# wireless-therm-mk1.net
KiCad netlist of a schematic drawn in EAGLE
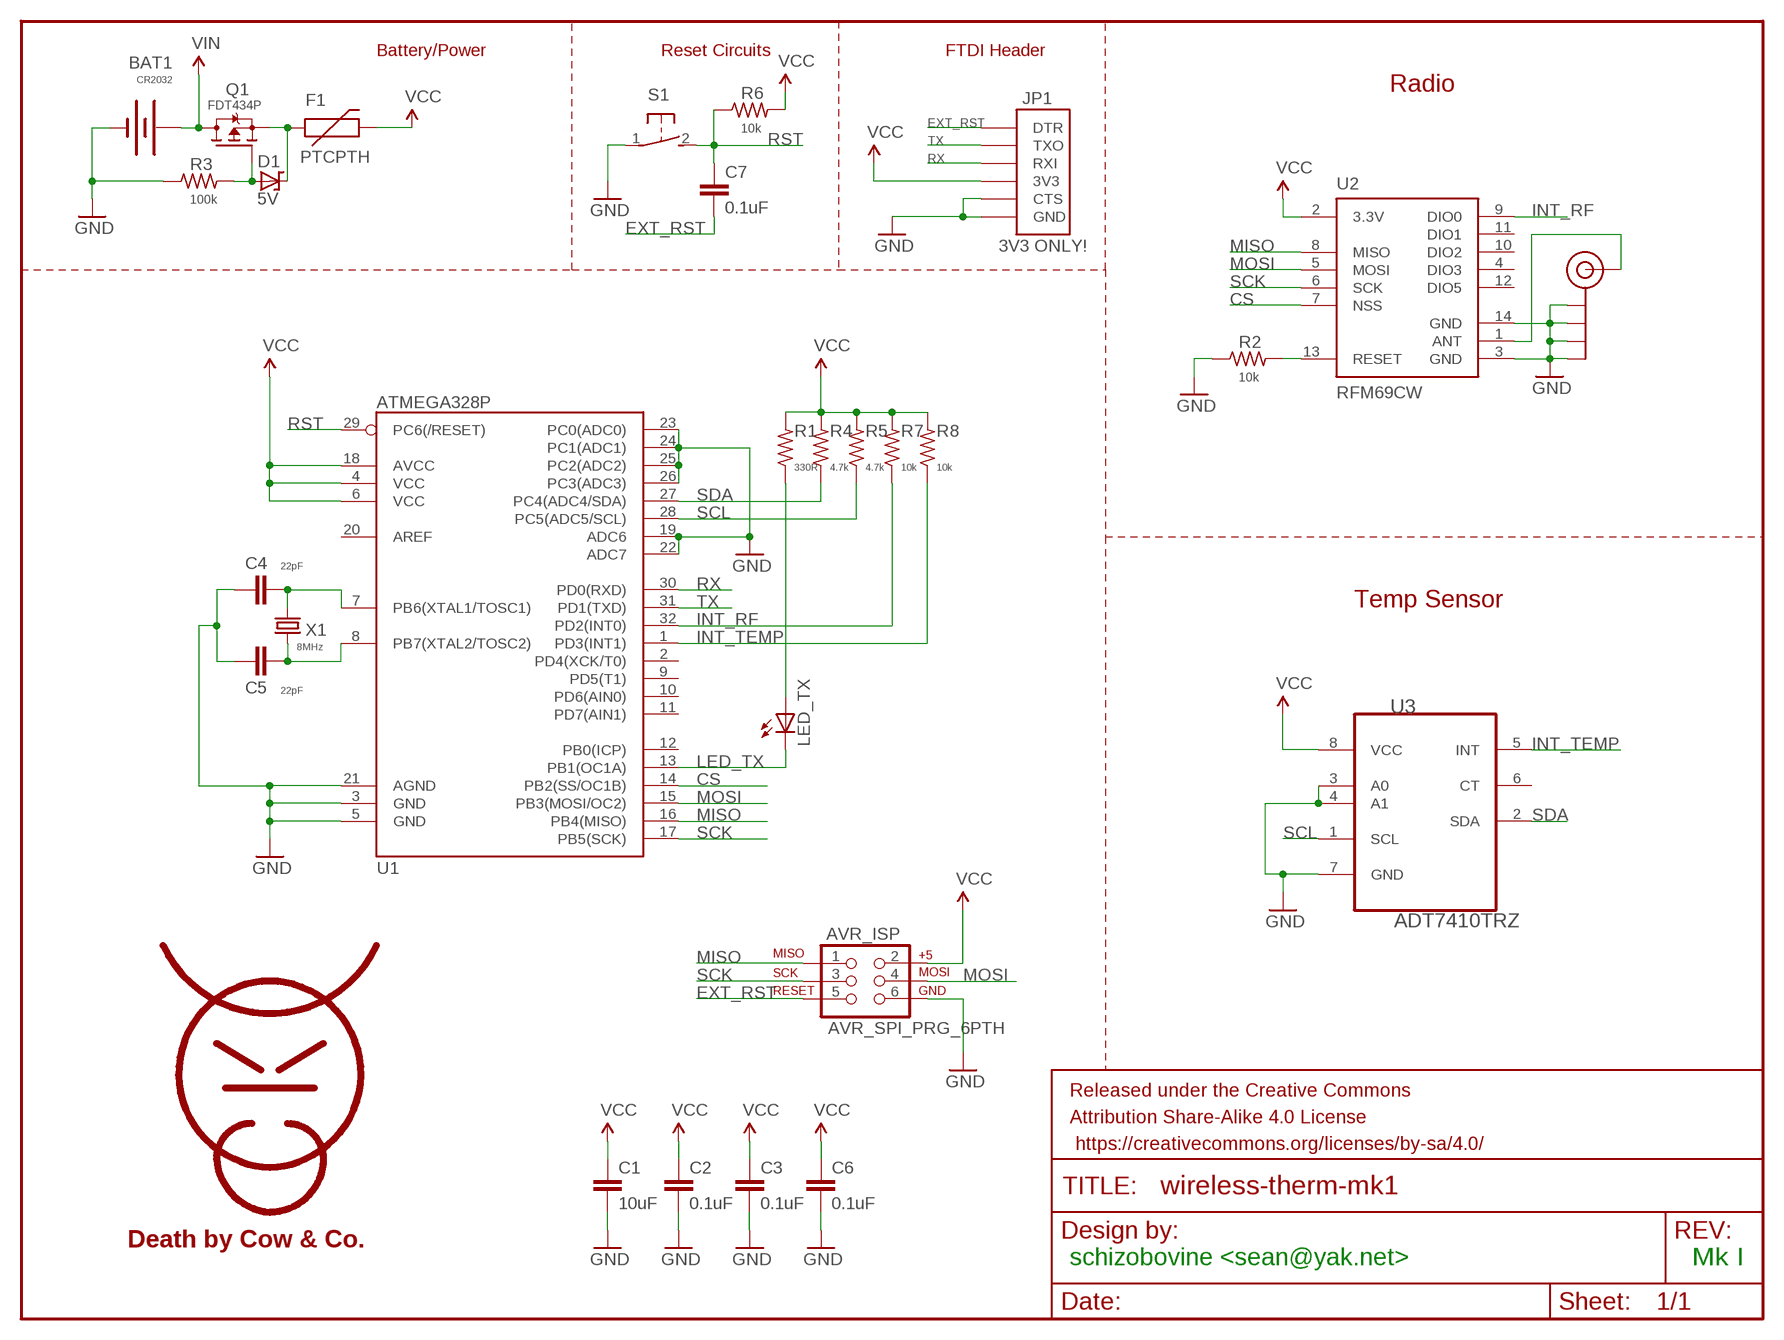
[diagram p0: schematic, sheet 1]

(export (version "E")
  (design (tool "Eeschema 10.0.6"))
  (components
    (comp (ref "AVR_ISP")
      (value "AVR_SPI_PRG_6PTH")
      (footprint "eagle-import:2X3")
      (libsource (lib "eagle-import") (part "AVR_SPI_PRG_6PTH"))
    )
    (comp (ref "BAT1")
      (value "CR2032")
      (footprint "eagle-import:BATTCON_20MM")
      (libsource (lib "eagle-import") (part "BATTERY20SMD"))
    )
    (comp (ref "C1")
      (value "10uF")
      (footprint "eagle-import:C050-025X075")
      (libsource (lib "eagle-import") (part "CAPACITOR-CERAMIC050-025X075"))
    )
    (comp (ref "C2")
      (value "0.1uF")
      (footprint "eagle-import:C025-024X044")
      (libsource (lib "eagle-import") (part "CAPACITOR-CERAMIC025-024X044"))
    )
    (comp (ref "C3")
      (value "0.1uF")
      (footprint "eagle-import:C025-024X044")
      (libsource (lib "eagle-import") (part "CAPACITOR-CERAMIC025-024X044"))
    )
    (comp (ref "C4")
      (value "22pF")
      (footprint "eagle-import:C025-025X050")
      (libsource (lib "eagle-import") (part "C-EU025-025X050"))
    )
    (comp (ref "C5")
      (value "22pF")
      (footprint "eagle-import:C025-025X050")
      (libsource (lib "eagle-import") (part "C-EU025-025X050"))
    )
    (comp (ref "C6")
      (value "0.1uF")
      (footprint "eagle-import:C025-024X044")
      (libsource (lib "eagle-import") (part "CAPACITOR-CERAMIC025-024X044"))
    )
    (comp (ref "C7")
      (value "0.1uF")
      (footprint "eagle-import:C025-024X044")
      (libsource (lib "eagle-import") (part "CAPACITOR-CERAMIC025-024X044"))
    )
    (comp (ref "D1")
      (value "5V")
      (footprint "eagle-import:DO34Z7")
      (libsource (lib "eagle-import") (part "DO-34ZDO-34Z"))
    )
    (comp (ref "F1")
      (value "PTCPTH")
      (footprint "eagle-import:PTC")
      (libsource (lib "eagle-import") (part "PTCPTH"))
    )
    (comp (ref "FRAME1")
      (value "FRAME-LETTER")
      (footprint "eagle-import:CREATIVE_COMMONS")
      (libsource (lib "eagle-import") (part "FRAME-LETTER"))
    )
    (comp (ref "JP1")
      (value "3V3 ONLY!")
      (footprint "eagle-import:FTDI_3V3")
      (libsource (lib "eagle-import") (part "FTDI_3V3"))
    )
    (comp (ref "LED_TX")
      (value "GREEN")
      (footprint "eagle-import:LED3MM")
      (libsource (lib "eagle-import") (part "LED3MM"))
    )
    (comp (ref "Q1")
      (value "FDT434P")
      (footprint "eagle-import:SOT223")
      (libsource (lib "eagle-import") (part "FDT434P"))
    )
    (comp (ref "R1")
      (value "330R")
      (footprint "eagle-import:0204_5")
      (libsource (lib "eagle-import") (part "R-US_0204/5"))
    )
    (comp (ref "R2")
      (value "10k")
      (footprint "eagle-import:0204_5")
      (libsource (lib "eagle-import") (part "R-US_0204/5"))
    )
    (comp (ref "R3")
      (value "100k")
      (footprint "eagle-import:0204_5")
      (libsource (lib "eagle-import") (part "R-US_0204/5"))
    )
    (comp (ref "R4")
      (value "4.7k")
      (footprint "eagle-import:0204_5")
      (libsource (lib "eagle-import") (part "R-US_0204/5"))
    )
    (comp (ref "R5")
      (value "4.7k")
      (footprint "eagle-import:0204_5")
      (libsource (lib "eagle-import") (part "R-US_0204/5"))
    )
    (comp (ref "R6")
      (value "10k")
      (footprint "eagle-import:0204_5")
      (libsource (lib "eagle-import") (part "R-US_0204/5"))
    )
    (comp (ref "R7")
      (value "10k")
      (footprint "eagle-import:0204_5")
      (libsource (lib "eagle-import") (part "R-US_0204/5"))
    )
    (comp (ref "R8")
      (value "10k")
      (footprint "eagle-import:0204_5")
      (libsource (lib "eagle-import") (part "R-US_0204/5"))
    )
    (comp (ref "S1")
      (value "DTS-3")
      (footprint "eagle-import:DTS-3")
      (libsource (lib "eagle-import") (part "DTS-3"))
    )
    (comp (ref "SMA_CON")
      (value "SMA_EDGE")
      (footprint "eagle-import:SMA-EDGE")
      (libsource (lib "eagle-import") (part "SMA_EDGE"))
    )
    (comp (ref "U$4")
      (value "COW")
      (footprint "eagle-import:COW")
      (libsource (lib "eagle-import") (part "COW"))
    )
    (comp (ref "U1")
      (value "ATMEGA328P")
      (footprint "eagle-import:TQFP32-08")
      (libsource (lib "eagle-import") (part "ATMEGA328_SMT"))
    )
    (comp (ref "U2")
      (value "RFM69CW")
      (footprint "eagle-import:RFM69CW-XXXS2")
      (libsource (lib "eagle-import") (part "RFM69CW"))
    )
    (comp (ref "U3")
      (value "ADT7410TRZ")
      (footprint "eagle-import:SOIC127P600X175-8N")
      (libsource (lib "eagle-import") (part "ADT7410TRZ"))
    )
    (comp (ref "X1")
      (value "8MHz")
      (footprint "eagle-import:HC49U70")
      (libsource (lib "eagle-import") (part "CRYSTALHC49U70"))
    )
  )
  (nets
    (net (code "1") (name "/CS") (class "Default")
      (node (ref "U1") (pin "14") (pinfunction "PB2(SS/OC1B)_14") (pintype "bidirectional"))
      (node (ref "U2") (pin "7") (pinfunction "NSS_7") (pintype "input"))
    )
    (net (code "2") (name "/EXT_RST") (class "Default")
      (node (ref "AVR_ISP") (pin "5") (pinfunction "5_5") (pintype "passive"))
      (node (ref "C7") (pin "2") (pinfunction "2_2") (pintype "passive"))
      (node (ref "JP1") (pin "P$1") (pinfunction "DTR_P$1") (pintype "bidirectional"))
    )
    (net (code "3") (name "/INT_RF") (class "Default")
      (node (ref "R7") (pin "1") (pinfunction "1_1") (pintype "passive"))
      (node (ref "U1") (pin "32") (pinfunction "PD2(INT0)_32") (pintype "bidirectional"))
      (node (ref "U2") (pin "9") (pinfunction "DIO0_9") (pintype "bidirectional"))
    )
    (net (code "4") (name "/INT_TEMP") (class "Default")
      (node (ref "R8") (pin "1") (pinfunction "1_1") (pintype "passive"))
      (node (ref "U1") (pin "1") (pinfunction "PD3(INT1)_1") (pintype "bidirectional"))
      (node (ref "U3") (pin "5") (pinfunction "INT_5") (pintype "output"))
    )
    (net (code "5") (name "/LED_TX") (class "Default")
      (node (ref "LED_TX") (pin "K") (pinfunction "C_K") (pintype "passive"))
      (node (ref "U1") (pin "13") (pinfunction "PB1(OC1A)_13") (pintype "bidirectional"))
    )
    (net (code "6") (name "/MISO") (class "Default")
      (node (ref "AVR_ISP") (pin "1") (pinfunction "1_1") (pintype "passive"))
      (node (ref "U1") (pin "16") (pinfunction "PB4(MISO)_16") (pintype "bidirectional"))
      (node (ref "U2") (pin "8") (pinfunction "MISO_8") (pintype "bidirectional"))
    )
    (net (code "7") (name "/MOSI") (class "Default")
      (node (ref "AVR_ISP") (pin "4") (pinfunction "4_4") (pintype "passive"))
      (node (ref "U1") (pin "15") (pinfunction "PB3(MOSI/OC2)_15") (pintype "bidirectional"))
      (node (ref "U2") (pin "5") (pinfunction "MOSI_5") (pintype "input"))
    )
    (net (code "8") (name "/RST") (class "Default")
      (node (ref "C7") (pin "1") (pinfunction "1_1") (pintype "passive"))
      (node (ref "R6") (pin "1") (pinfunction "1_1") (pintype "passive"))
      (node (ref "S1") (pin "2") (pinfunction "2_2") (pintype "passive"))
      (node (ref "U1") (pin "29") (pinfunction "PC6(/RESET)_29") (pintype "bidirectional"))
    )
    (net (code "9") (name "/RX") (class "Default")
      (node (ref "JP1") (pin "P$3") (pinfunction "RXI_P$3") (pintype "bidirectional"))
      (node (ref "U1") (pin "30") (pinfunction "PD0(RXD)_30") (pintype "bidirectional"))
    )
    (net (code "10") (name "/SCK") (class "Default")
      (node (ref "AVR_ISP") (pin "3") (pinfunction "3_3") (pintype "passive"))
      (node (ref "U1") (pin "17") (pinfunction "PB5(SCK)_17") (pintype "bidirectional"))
      (node (ref "U2") (pin "6") (pinfunction "SCK_6") (pintype "input"))
    )
    (net (code "11") (name "/SCL") (class "Default")
      (node (ref "R5") (pin "1") (pinfunction "1_1") (pintype "passive"))
      (node (ref "U1") (pin "28") (pinfunction "PC5(ADC5/SCL)_28") (pintype "bidirectional"))
      (node (ref "U3") (pin "1") (pinfunction "SCL_1") (pintype "input"))
    )
    (net (code "12") (name "/SDA") (class "Default")
      (node (ref "R4") (pin "1") (pinfunction "1_1") (pintype "passive"))
      (node (ref "U1") (pin "27") (pinfunction "PC4(ADC4/SDA)_27") (pintype "bidirectional"))
      (node (ref "U3") (pin "2") (pinfunction "SDA_2") (pintype "bidirectional"))
    )
    (net (code "13") (name "/TX") (class "Default")
      (node (ref "JP1") (pin "P$2") (pinfunction "TXO_P$2") (pintype "bidirectional"))
      (node (ref "U1") (pin "31") (pinfunction "PD1(TXD)_31") (pintype "bidirectional"))
    )
    (net (code "14") (name "GND") (class "Default")
      (node (ref "AVR_ISP") (pin "6") (pinfunction "6_6") (pintype "passive"))
      (node (ref "BAT1") (pin "2") (pinfunction "-_2") (pintype "power_in"))
      (node (ref "C1") (pin "2") (pinfunction "2_2") (pintype "passive"))
      (node (ref "C2") (pin "2") (pinfunction "2_2") (pintype "passive"))
      (node (ref "C3") (pin "2") (pinfunction "2_2") (pintype "passive"))
      (node (ref "C4") (pin "1") (pinfunction "1_1") (pintype "passive"))
      (node (ref "C5") (pin "1") (pinfunction "1_1") (pintype "passive"))
      (node (ref "C6") (pin "2") (pinfunction "2_2") (pintype "passive"))
      (node (ref "JP1") (pin "P$5") (pinfunction "CTS_P$5") (pintype "bidirectional"))
      (node (ref "JP1") (pin "P$6") (pinfunction "GND_P$6") (pintype "bidirectional"))
      (node (ref "R2") (pin "1") (pinfunction "1_1") (pintype "passive"))
      (node (ref "R3") (pin "1") (pinfunction "1_1") (pintype "passive"))
      (node (ref "S1") (pin "1") (pinfunction "1_1") (pintype "passive"))
      (node (ref "SMA_CON") (pin "GND@0") (pinfunction "GND_GND@0") (pintype "bidirectional"))
      (node (ref "SMA_CON") (pin "GND@1") (pinfunction "GND_GND@1") (pintype "bidirectional"))
      (node (ref "SMA_CON") (pin "GND@2") (pinfunction "GND_GND@2") (pintype "bidirectional"))
      (node (ref "SMA_CON") (pin "GND@3") (pinfunction "GND_GND@3") (pintype "bidirectional"))
      (node (ref "U1") (pin "19") (pinfunction "ADC6_19") (pintype "bidirectional"))
      (node (ref "U1") (pin "21") (pinfunction "AGND_21") (pintype "bidirectional"))
      (node (ref "U1") (pin "22") (pinfunction "ADC7_22") (pintype "bidirectional"))
      (node (ref "U1") (pin "23") (pinfunction "PC0(ADC0)_23") (pintype "bidirectional"))
      (node (ref "U1") (pin "24") (pinfunction "PC1(ADC1)_24") (pintype "bidirectional"))
      (node (ref "U1") (pin "25") (pinfunction "PC2(ADC2)_25") (pintype "bidirectional"))
      (node (ref "U1") (pin "26") (pinfunction "PC3(ADC3)_26") (pintype "bidirectional"))
      (node (ref "U1") (pin "3") (pinfunction "GND_3") (pintype "bidirectional"))
      (node (ref "U1") (pin "5") (pinfunction "GND_5") (pintype "bidirectional"))
      (node (ref "U2") (pin "14") (pinfunction "GND_14") (pintype "power_in"))
      (node (ref "U2") (pin "3") (pinfunction "GND_3") (pintype "power_in"))
      (node (ref "U3") (pin "3") (pinfunction "A0_3") (pintype "input"))
      (node (ref "U3") (pin "4") (pinfunction "A1_4") (pintype "input"))
      (node (ref "U3") (pin "7") (pinfunction "GND_7") (pintype "passive"))
    )
    (net (code "15") (name "Net-(F1-1)") (class "Default")
      (node (ref "D1") (pin "C") (pinfunction "C_C") (pintype "passive"))
      (node (ref "F1") (pin "P$1") (pinfunction "1_P$1") (pintype "bidirectional"))
      (node (ref "Q1") (pin "3") (pinfunction "S_3") (pintype "passive"))
    )
    (net (code "16") (name "Net-(LED_TX-PadA)") (class "Default")
      (node (ref "LED_TX") (pin "A") (pinfunction "A_A") (pintype "passive"))
      (node (ref "R1") (pin "1") (pinfunction "1_1") (pintype "passive"))
    )
    (net (code "17") (name "Net-(Q1-G)") (class "Default")
      (node (ref "D1") (pin "A") (pinfunction "A_A") (pintype "passive"))
      (node (ref "Q1") (pin "1") (pinfunction "G_1") (pintype "passive"))
      (node (ref "R3") (pin "2") (pinfunction "2_2") (pintype "passive"))
    )
    (net (code "18") (name "Net-(SMA_CON-SIGNAL)") (class "Default")
      (node (ref "SMA_CON") (pin "SIG") (pinfunction "SIGNAL_SIG") (pintype "bidirectional"))
      (node (ref "U2") (pin "1") (pinfunction "ANT_1") (pintype "passive"))
    )
    (net (code "19") (name "Net-(U1-PB6(XTAL1{slash}TOSC1))") (class "Default")
      (node (ref "C4") (pin "2") (pinfunction "2_2") (pintype "passive"))
      (node (ref "U1") (pin "7") (pinfunction "PB6(XTAL1/TOSC1)_7") (pintype "bidirectional"))
      (node (ref "X1") (pin "2") (pinfunction "2_2") (pintype "passive"))
    )
    (net (code "20") (name "Net-(U1-PB7(XTAL2{slash}TOSC2))") (class "Default")
      (node (ref "C5") (pin "2") (pinfunction "2_2") (pintype "passive"))
      (node (ref "U1") (pin "8") (pinfunction "PB7(XTAL2/TOSC2)_8") (pintype "bidirectional"))
      (node (ref "X1") (pin "1") (pinfunction "1_1") (pintype "passive"))
    )
    (net (code "21") (name "Net-(U2-RESET)") (class "Default")
      (node (ref "R2") (pin "2") (pinfunction "2_2") (pintype "passive"))
      (node (ref "U2") (pin "13") (pinfunction "RESET_13") (pintype "input"))
    )
    (net (code "22") (name "VCC") (class "Default")
      (node (ref "AVR_ISP") (pin "2") (pinfunction "2_2") (pintype "passive"))
      (node (ref "C1") (pin "1") (pinfunction "1_1") (pintype "passive"))
      (node (ref "C2") (pin "1") (pinfunction "1_1") (pintype "passive"))
      (node (ref "C3") (pin "1") (pinfunction "1_1") (pintype "passive"))
      (node (ref "C6") (pin "1") (pinfunction "1_1") (pintype "passive"))
      (node (ref "F1") (pin "P$2") (pinfunction "2_P$2") (pintype "bidirectional"))
      (node (ref "JP1") (pin "P$4") (pinfunction "3V3_P$4") (pintype "bidirectional"))
      (node (ref "R1") (pin "2") (pinfunction "2_2") (pintype "passive"))
      (node (ref "R4") (pin "2") (pinfunction "2_2") (pintype "passive"))
      (node (ref "R5") (pin "2") (pinfunction "2_2") (pintype "passive"))
      (node (ref "R6") (pin "2") (pinfunction "2_2") (pintype "passive"))
      (node (ref "R7") (pin "2") (pinfunction "2_2") (pintype "passive"))
      (node (ref "R8") (pin "2") (pinfunction "2_2") (pintype "passive"))
      (node (ref "U1") (pin "18") (pinfunction "AVCC_18") (pintype "bidirectional"))
      (node (ref "U1") (pin "4") (pinfunction "VCC_4") (pintype "bidirectional"))
      (node (ref "U1") (pin "6") (pinfunction "VCC_6") (pintype "bidirectional"))
      (node (ref "U2") (pin "2") (pinfunction "3.3V_2") (pintype "power_in"))
      (node (ref "U3") (pin "8") (pinfunction "VCC_8") (pintype "power_in"))
    )
    (net (code "23") (name "VIN") (class "Default")
      (node (ref "BAT1") (pin "1") (pinfunction "+_1") (pintype "power_in"))
      (node (ref "BAT1") (pin "3") (pinfunction "+_3") (pintype "power_in"))
      (node (ref "Q1") (pin "2") (pinfunction "D_2") (pintype "passive"))
      (node (ref "Q1") (pin "4") (pinfunction "D_4") (pintype "passive"))
    )
    (net (code "24") (name "unconnected-(U1-AREF-Pad20)") (class "Default")
      (node (ref "U1") (pin "20") (pinfunction "AREF_20") (pintype "bidirectional"))
    )
    (net (code "25") (name "unconnected-(U1-PB0(ICP)-Pad12)") (class "Default")
      (node (ref "U1") (pin "12") (pinfunction "PB0(ICP)_12") (pintype "bidirectional"))
    )
    (net (code "26") (name "unconnected-(U1-PD4(XCK{slash}T0)-Pad2)") (class "Default")
      (node (ref "U1") (pin "2") (pinfunction "PD4(XCK/T0)_2") (pintype "bidirectional"))
    )
    (net (code "27") (name "unconnected-(U1-PD5(T1)-Pad9)") (class "Default")
      (node (ref "U1") (pin "9") (pinfunction "PD5(T1)_9") (pintype "bidirectional"))
    )
    (net (code "28") (name "unconnected-(U1-PD6(AIN0)-Pad10)") (class "Default")
      (node (ref "U1") (pin "10") (pinfunction "PD6(AIN0)_10") (pintype "bidirectional"))
    )
    (net (code "29") (name "unconnected-(U1-PD7(AIN1)-Pad11)") (class "Default")
      (node (ref "U1") (pin "11") (pinfunction "PD7(AIN1)_11") (pintype "bidirectional"))
    )
    (net (code "30") (name "unconnected-(U2-DIO1-Pad11)") (class "Default")
      (node (ref "U2") (pin "11") (pinfunction "DIO1_11") (pintype "bidirectional"))
    )
    (net (code "31") (name "unconnected-(U2-DIO2-Pad10)") (class "Default")
      (node (ref "U2") (pin "10") (pinfunction "DIO2_10") (pintype "bidirectional"))
    )
    (net (code "32") (name "unconnected-(U2-DIO3-Pad4)") (class "Default")
      (node (ref "U2") (pin "4") (pinfunction "DIO3_4") (pintype "bidirectional"))
    )
    (net (code "33") (name "unconnected-(U2-DIO5-Pad12)") (class "Default")
      (node (ref "U2") (pin "12") (pinfunction "DIO5_12") (pintype "bidirectional"))
    )
    (net (code "34") (name "unconnected-(U3-CT-Pad6)") (class "Default")
      (node (ref "U3") (pin "6") (pinfunction "CT_6") (pintype "output"))
    )
  )
)
